# general_purpose_to247_hbridge_rev2.net
KiCad netlist of a schematic drawn in EAGLE
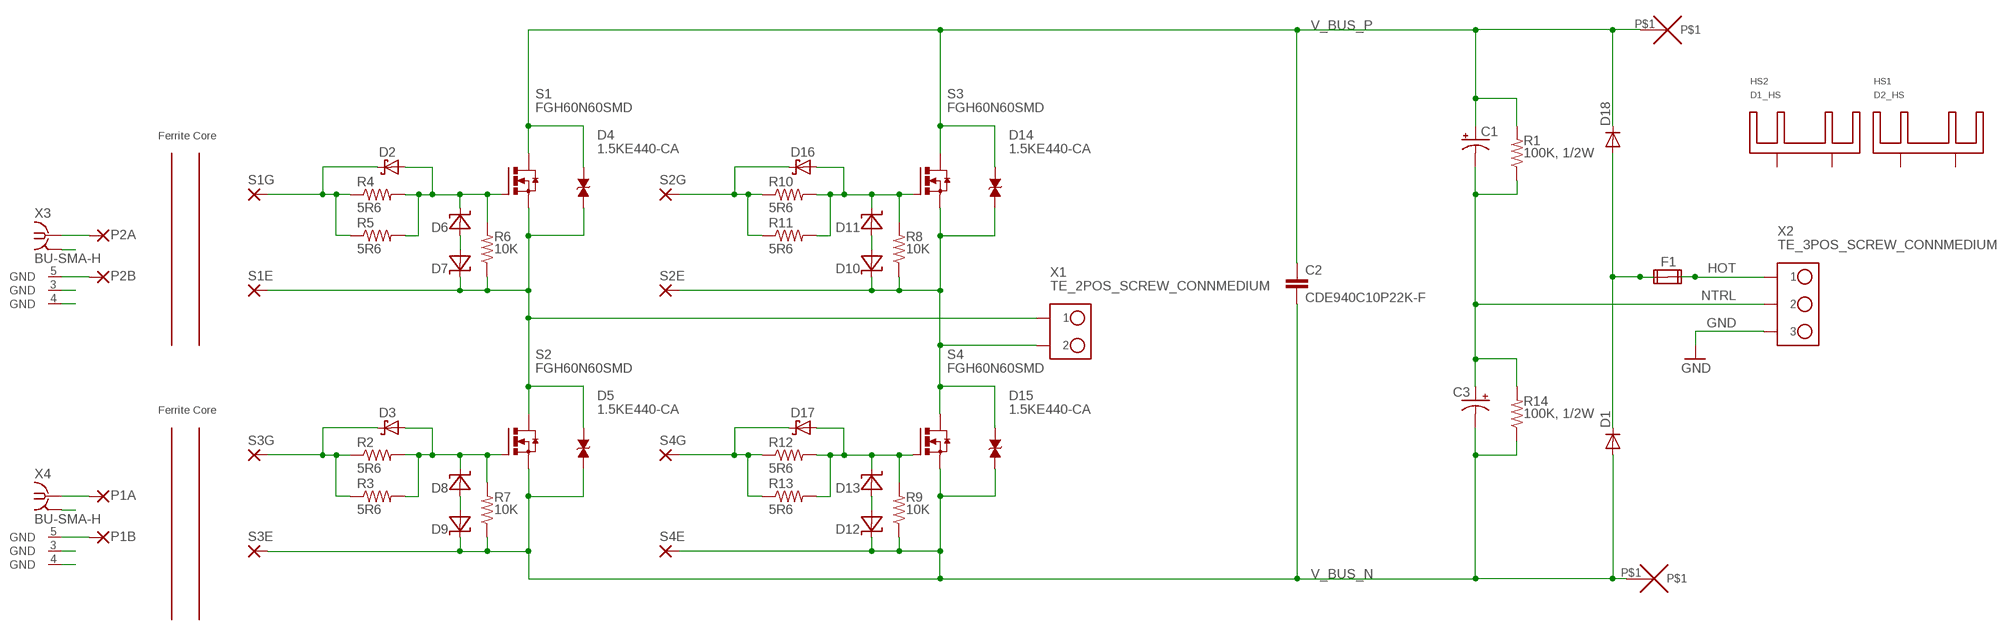
[diagram p0: schematic, sheet 1]

(export (version "E")
  (design (tool "Eeschema 10.0.6"))
  (components
    (comp (ref "C1")
      (value "CPOL-USE10-35")
      (footprint "eagle-import:EB35D")
      (libsource (lib "eagle-import") (part "CPOL-USE10-35"))
    )
    (comp (ref "C2")
      (value "CDE940C10P22K-F")
      (footprint "eagle-import:940C10P22K-F")
      (libsource (lib "eagle-import") (part "CDE940C10P22K-F"))
    )
    (comp (ref "C3")
      (value "CPOL-USE10-35")
      (footprint "eagle-import:EB35D")
      (libsource (lib "eagle-import") (part "CPOL-USE10-35"))
    )
    (comp (ref "D1")
      (value "DIODE-DO220S")
      (footprint "eagle-import:DO220S")
      (libsource (lib "eagle-import") (part "DIODE-DO220S"))
    )
    (comp (ref "D2")
      (value "SCHOTTKY_SMA")
      (footprint "eagle-import:SMA")
      (libsource (lib "eagle-import") (part "SCHOTTKY_SMA"))
    )
    (comp (ref "D3")
      (value "SCHOTTKY_SMA")
      (footprint "eagle-import:SMA")
      (libsource (lib "eagle-import") (part "SCHOTTKY_SMA"))
    )
    (comp (ref "D4")
      (value "1.5KE440-CA")
      (footprint "eagle-import:DO-201_BI")
      (libsource (lib "eagle-import") (part "1.5KEXXX-CA"))
    )
    (comp (ref "D5")
      (value "1.5KE440-CA")
      (footprint "eagle-import:DO-201_BI")
      (libsource (lib "eagle-import") (part "1.5KEXXX-CA"))
    )
    (comp (ref "D6")
      (value "ZENER_SMA")
      (footprint "eagle-import:SMA")
      (libsource (lib "eagle-import") (part "ZENER_SMA"))
    )
    (comp (ref "D7")
      (value "ZENER_SMA")
      (footprint "eagle-import:SMA")
      (libsource (lib "eagle-import") (part "ZENER_SMA"))
    )
    (comp (ref "D8")
      (value "ZENER_SMA")
      (footprint "eagle-import:SMA")
      (libsource (lib "eagle-import") (part "ZENER_SMA"))
    )
    (comp (ref "D9")
      (value "ZENER_SMA")
      (footprint "eagle-import:SMA")
      (libsource (lib "eagle-import") (part "ZENER_SMA"))
    )
    (comp (ref "D10")
      (value "ZENER_SMA")
      (footprint "eagle-import:SMA")
      (libsource (lib "eagle-import") (part "ZENER_SMA"))
    )
    (comp (ref "D11")
      (value "ZENER_SMA")
      (footprint "eagle-import:SMA")
      (libsource (lib "eagle-import") (part "ZENER_SMA"))
    )
    (comp (ref "D12")
      (value "ZENER_SMA")
      (footprint "eagle-import:SMA")
      (libsource (lib "eagle-import") (part "ZENER_SMA"))
    )
    (comp (ref "D13")
      (value "ZENER_SMA")
      (footprint "eagle-import:SMA")
      (libsource (lib "eagle-import") (part "ZENER_SMA"))
    )
    (comp (ref "D14")
      (value "1.5KE440-CA")
      (footprint "eagle-import:DO-201_BI")
      (libsource (lib "eagle-import") (part "1.5KEXXX-CA"))
    )
    (comp (ref "D15")
      (value "1.5KE440-CA")
      (footprint "eagle-import:DO-201_BI")
      (libsource (lib "eagle-import") (part "1.5KEXXX-CA"))
    )
    (comp (ref "D16")
      (value "SCHOTTKY_SMA")
      (footprint "eagle-import:SMA")
      (libsource (lib "eagle-import") (part "SCHOTTKY_SMA"))
    )
    (comp (ref "D17")
      (value "SCHOTTKY_SMA")
      (footprint "eagle-import:SMA")
      (libsource (lib "eagle-import") (part "SCHOTTKY_SMA"))
    )
    (comp (ref "D18")
      (value "DIODE-DO220S")
      (footprint "eagle-import:DO220S")
      (libsource (lib "eagle-import") (part "DIODE-DO220S"))
    )
    (comp (ref "F1")
      (value "FUSE2P")
      (footprint "eagle-import:FUSE1")
      (libsource (lib "eagle-import") (part "FUSE2P"))
    )
    (comp (ref "HS1")
      (value "D2_HS")
      (footprint "eagle-import:V6560_HEATSINK_REVERSED")
      (libsource (lib "eagle-import") (part "HEATSINK_V6560R"))
    )
    (comp (ref "HS2")
      (value "D1_HS")
      (footprint "eagle-import:V6560_HEATSINK_REVERSED")
      (libsource (lib "eagle-import") (part "HEATSINK_V6560R"))
    )
    (comp (ref "P1A")
      (value "SMD5")
      (footprint "eagle-import:SMD2,54-5,08")
      (libsource (lib "eagle-import") (part "SMD5"))
    )
    (comp (ref "P1B")
      (value "SMD5")
      (footprint "eagle-import:SMD2,54-5,08")
      (libsource (lib "eagle-import") (part "SMD5"))
    )
    (comp (ref "P2A")
      (value "SMD5")
      (footprint "eagle-import:SMD2,54-5,08")
      (libsource (lib "eagle-import") (part "SMD5"))
    )
    (comp (ref "P2B")
      (value "SMD5")
      (footprint "eagle-import:SMD2,54-5,08")
      (libsource (lib "eagle-import") (part "SMD5"))
    )
    (comp (ref "R1")
      (value "100K, 1/2W")
      (footprint "eagle-import:0309_12")
      (libsource (lib "eagle-import") (part "R-US_0309/12"))
    )
    (comp (ref "R2")
      (value "5R6")
      (footprint "eagle-import:R2010")
      (libsource (lib "eagle-import") (part "R-US_R2010"))
    )
    (comp (ref "R3")
      (value "5R6")
      (footprint "eagle-import:R0805")
      (libsource (lib "eagle-import") (part "R-US_R0805"))
    )
    (comp (ref "R4")
      (value "5R6")
      (footprint "eagle-import:R2010")
      (libsource (lib "eagle-import") (part "R-US_R2010"))
    )
    (comp (ref "R5")
      (value "5R6")
      (footprint "eagle-import:R0805")
      (libsource (lib "eagle-import") (part "R-US_R0805"))
    )
    (comp (ref "R6")
      (value "10K")
      (footprint "eagle-import:R0805")
      (libsource (lib "eagle-import") (part "R-US_R0805"))
    )
    (comp (ref "R7")
      (value "10K")
      (footprint "eagle-import:R0805")
      (libsource (lib "eagle-import") (part "R-US_R0805"))
    )
    (comp (ref "R8")
      (value "10K")
      (footprint "eagle-import:R0805")
      (libsource (lib "eagle-import") (part "R-US_R0805"))
    )
    (comp (ref "R9")
      (value "10K")
      (footprint "eagle-import:R0805")
      (libsource (lib "eagle-import") (part "R-US_R0805"))
    )
    (comp (ref "R10")
      (value "5R6")
      (footprint "eagle-import:R2010")
      (libsource (lib "eagle-import") (part "R-US_R2010"))
    )
    (comp (ref "R11")
      (value "5R6")
      (footprint "eagle-import:R0805")
      (libsource (lib "eagle-import") (part "R-US_R0805"))
    )
    (comp (ref "R12")
      (value "5R6")
      (footprint "eagle-import:R2010")
      (libsource (lib "eagle-import") (part "R-US_R2010"))
    )
    (comp (ref "R13")
      (value "5R6")
      (footprint "eagle-import:R0805")
      (libsource (lib "eagle-import") (part "R-US_R0805"))
    )
    (comp (ref "R14")
      (value "100K, 1/2W")
      (footprint "eagle-import:0309_12")
      (libsource (lib "eagle-import") (part "R-US_0309/12"))
    )
    (comp (ref "S1")
      (value "FGH60N60SMD")
      (footprint "eagle-import:TO247_H_NOHOLE")
      (libsource (lib "eagle-import") (part "MOSFET-N_TO247"))
    )
    (comp (ref "S1E")
      (value "SMD5")
      (footprint "eagle-import:SMD2,54-5,08")
      (libsource (lib "eagle-import") (part "SMD5"))
    )
    (comp (ref "S1G")
      (value "SMD5")
      (footprint "eagle-import:SMD2,54-5,08")
      (libsource (lib "eagle-import") (part "SMD5"))
    )
    (comp (ref "S2")
      (value "FGH60N60SMD")
      (footprint "eagle-import:TO247_H_NOHOLE")
      (libsource (lib "eagle-import") (part "MOSFET-N_TO247"))
    )
    (comp (ref "S2E")
      (value "SMD5")
      (footprint "eagle-import:SMD2,54-5,08")
      (libsource (lib "eagle-import") (part "SMD5"))
    )
    (comp (ref "S2G")
      (value "SMD5")
      (footprint "eagle-import:SMD2,54-5,08")
      (libsource (lib "eagle-import") (part "SMD5"))
    )
    (comp (ref "S3")
      (value "FGH60N60SMD")
      (footprint "eagle-import:TO247_H_NOHOLE")
      (libsource (lib "eagle-import") (part "MOSFET-N_TO247"))
    )
    (comp (ref "S3E")
      (value "SMD5")
      (footprint "eagle-import:SMD2,54-5,08")
      (libsource (lib "eagle-import") (part "SMD5"))
    )
    (comp (ref "S3G")
      (value "SMD5")
      (footprint "eagle-import:SMD2,54-5,08")
      (libsource (lib "eagle-import") (part "SMD5"))
    )
    (comp (ref "S4")
      (value "FGH60N60SMD")
      (footprint "eagle-import:TO247_H_NOHOLE")
      (libsource (lib "eagle-import") (part "MOSFET-N_TO247"))
    )
    (comp (ref "S4E")
      (value "SMD5")
      (footprint "eagle-import:SMD2,54-5,08")
      (libsource (lib "eagle-import") (part "SMD5"))
    )
    (comp (ref "S4G")
      (value "SMD5")
      (footprint "eagle-import:SMD2,54-5,08")
      (libsource (lib "eagle-import") (part "SMD5"))
    )
    (comp (ref "U$1")
      (value "12AWG_PAD")
      (footprint "eagle-import:12AWG_PAD")
      (libsource (lib "eagle-import") (part "12AWG_PAD"))
    )
    (comp (ref "U$2")
      (value "GDT_SYMBOL")
      (footprint "eagle-import:GDT")
      (libsource (lib "eagle-import") (part "GDT_SYMBOL"))
    )
    (comp (ref "U$3")
      (value "12AWG_PAD")
      (footprint "eagle-import:12AWG_PAD")
      (libsource (lib "eagle-import") (part "12AWG_PAD"))
    )
    (comp (ref "U$4")
      (value "GDT_SYMBOL")
      (footprint "eagle-import:GDT")
      (libsource (lib "eagle-import") (part "GDT_SYMBOL"))
    )
    (comp (ref "X1")
      (value "TE_2POS_SCREW_CONNMEDIUM")
      (footprint "eagle-import:OST_2POS_SCREW_CON_OSTYK51102030")
      (libsource (lib "eagle-import") (part "TE_2POS_SCREW_CONNMEDIUM"))
    )
    (comp (ref "X2")
      (value "TE_3POS_SCREW_CONNMEDIUM")
      (footprint "eagle-import:OST_2POS_SCREW_CON_SOTYK51103030")
      (libsource (lib "eagle-import") (part "TE_3POS_SCREW_CONNMEDIUM"))
    )
    (comp (ref "X3")
      (value "BU-SMA-H")
      (footprint "eagle-import:BU-SMA-H")
      (libsource (lib "eagle-import") (part "BU-SMA-H"))
    )
    (comp (ref "X4")
      (value "BU-SMA-H")
      (footprint "eagle-import:BU-SMA-H")
      (libsource (lib "eagle-import") (part "BU-SMA-H"))
    )
  )
  (nets
    (net (code "1") (name "/HOT") (class "Default")
      (node (ref "F1") (pin "2A") (pinfunction "2A_2A") (pintype "passive"))
      (node (ref "F1") (pin "2B") (pinfunction "2B_2B") (pintype "passive"))
      (node (ref "X2") (pin "P$1") (pinfunction "1_P$1") (pintype "bidirectional"))
    )
    (net (code "2") (name "/NTRL") (class "Default")
      (node (ref "C1") (pin "-") (pinfunction "-_-") (pintype "passive"))
      (node (ref "C3") (pin "+") (pinfunction "+_+") (pintype "passive"))
      (node (ref "R1") (pin "1") (pinfunction "1_1") (pintype "passive"))
      (node (ref "R14") (pin "2") (pinfunction "2_2") (pintype "passive"))
      (node (ref "X2") (pin "P$2") (pinfunction "2_P$2") (pintype "bidirectional"))
    )
    (net (code "3") (name "/V_BUS_N") (class "Default")
      (node (ref "C2") (pin "P$2") (pinfunction "2_P$2") (pintype "passive"))
      (node (ref "C3") (pin "-") (pinfunction "-_-") (pintype "passive"))
      (node (ref "D1") (pin "A") (pinfunction "A_A") (pintype "passive"))
      (node (ref "D12") (pin "C") (pinfunction "C_C") (pintype "passive"))
      (node (ref "D15") (pin "A") (pinfunction "P$1_A") (pintype "bidirectional"))
      (node (ref "D5") (pin "A") (pinfunction "P$1_A") (pintype "bidirectional"))
      (node (ref "D9") (pin "C") (pinfunction "C_C") (pintype "passive"))
      (node (ref "R14") (pin "1") (pinfunction "1_1") (pintype "passive"))
      (node (ref "R7") (pin "1") (pinfunction "1_1") (pintype "passive"))
      (node (ref "R9") (pin "1") (pinfunction "1_1") (pintype "passive"))
      (node (ref "S2") (pin "S") (pinfunction "S_S") (pintype "passive"))
      (node (ref "S3E") (pin "1") (pinfunction "P_1") (pintype "passive"))
      (node (ref "S4") (pin "S") (pinfunction "S_S") (pintype "passive"))
      (node (ref "S4E") (pin "1") (pinfunction "P_1") (pintype "passive"))
      (node (ref "U$1") (pin "P$1") (pinfunction "P$1_P$1") (pintype "bidirectional"))
    )
    (net (code "4") (name "/V_BUS_P") (class "Default")
      (node (ref "C1") (pin "+") (pinfunction "+_+") (pintype "passive"))
      (node (ref "C2") (pin "P$1") (pinfunction "1_P$1") (pintype "passive"))
      (node (ref "D14") (pin "C") (pinfunction "P$2_C") (pintype "bidirectional"))
      (node (ref "D18") (pin "C") (pinfunction "C_C") (pintype "passive"))
      (node (ref "D4") (pin "C") (pinfunction "P$2_C") (pintype "bidirectional"))
      (node (ref "R1") (pin "2") (pinfunction "2_2") (pintype "passive"))
      (node (ref "S1") (pin "D") (pinfunction "D_D") (pintype "passive"))
      (node (ref "S3") (pin "D") (pinfunction "D_D") (pintype "passive"))
      (node (ref "U$3") (pin "P$1") (pinfunction "P$1_P$1") (pintype "bidirectional"))
    )
    (net (code "5") (name "GND") (class "Default")
      (node (ref "X2") (pin "P$3") (pinfunction "3_P$3") (pintype "bidirectional"))
    )
    (net (code "6") (name "Net-(D1-PadC)") (class "Default")
      (node (ref "D1") (pin "C") (pinfunction "C_C") (pintype "passive"))
      (node (ref "D18") (pin "A") (pinfunction "A_A") (pintype "passive"))
      (node (ref "F1") (pin "1A") (pinfunction "1A_1A") (pintype "passive"))
      (node (ref "F1") (pin "1B") (pinfunction "1B_1B") (pintype "passive"))
    )
    (net (code "7") (name "Net-(D2-PadA)") (class "Default")
      (node (ref "D2") (pin "A") (pinfunction "A_A") (pintype "passive"))
      (node (ref "D6") (pin "C") (pinfunction "C_C") (pintype "passive"))
      (node (ref "R4") (pin "2") (pinfunction "2_2") (pintype "passive"))
      (node (ref "R5") (pin "2") (pinfunction "2_2") (pintype "passive"))
      (node (ref "R6") (pin "2") (pinfunction "2_2") (pintype "passive"))
      (node (ref "S1") (pin "G") (pinfunction "G_G") (pintype "passive"))
    )
    (net (code "8") (name "Net-(D3-PadA)") (class "Default")
      (node (ref "D3") (pin "A") (pinfunction "A_A") (pintype "passive"))
      (node (ref "D8") (pin "C") (pinfunction "C_C") (pintype "passive"))
      (node (ref "R2") (pin "2") (pinfunction "2_2") (pintype "passive"))
      (node (ref "R3") (pin "2") (pinfunction "2_2") (pintype "passive"))
      (node (ref "R7") (pin "2") (pinfunction "2_2") (pintype "passive"))
      (node (ref "S2") (pin "G") (pinfunction "G_G") (pintype "passive"))
    )
    (net (code "9") (name "Net-(D4-P$1)") (class "Default")
      (node (ref "D4") (pin "A") (pinfunction "P$1_A") (pintype "bidirectional"))
      (node (ref "D5") (pin "C") (pinfunction "P$2_C") (pintype "bidirectional"))
      (node (ref "D7") (pin "C") (pinfunction "C_C") (pintype "passive"))
      (node (ref "R6") (pin "1") (pinfunction "1_1") (pintype "passive"))
      (node (ref "S1") (pin "S") (pinfunction "S_S") (pintype "passive"))
      (node (ref "S1E") (pin "1") (pinfunction "P_1") (pintype "passive"))
      (node (ref "S2") (pin "D") (pinfunction "D_D") (pintype "passive"))
      (node (ref "X1") (pin "P$1") (pinfunction "1_P$1") (pintype "bidirectional"))
    )
    (net (code "10") (name "Net-(D6-PadA)") (class "Default")
      (node (ref "D6") (pin "A") (pinfunction "A_A") (pintype "passive"))
      (node (ref "D7") (pin "A") (pinfunction "A_A") (pintype "passive"))
    )
    (net (code "11") (name "Net-(D8-PadA)") (class "Default")
      (node (ref "D8") (pin "A") (pinfunction "A_A") (pintype "passive"))
      (node (ref "D9") (pin "A") (pinfunction "A_A") (pintype "passive"))
    )
    (net (code "12") (name "Net-(D10-PadA)") (class "Default")
      (node (ref "D10") (pin "A") (pinfunction "A_A") (pintype "passive"))
      (node (ref "D11") (pin "A") (pinfunction "A_A") (pintype "passive"))
    )
    (net (code "13") (name "Net-(D11-PadC)") (class "Default")
      (node (ref "D11") (pin "C") (pinfunction "C_C") (pintype "passive"))
      (node (ref "D16") (pin "A") (pinfunction "A_A") (pintype "passive"))
      (node (ref "R10") (pin "2") (pinfunction "2_2") (pintype "passive"))
      (node (ref "R11") (pin "2") (pinfunction "2_2") (pintype "passive"))
      (node (ref "R8") (pin "2") (pinfunction "2_2") (pintype "passive"))
      (node (ref "S3") (pin "G") (pinfunction "G_G") (pintype "passive"))
    )
    (net (code "14") (name "Net-(D12-PadA)") (class "Default")
      (node (ref "D12") (pin "A") (pinfunction "A_A") (pintype "passive"))
      (node (ref "D13") (pin "A") (pinfunction "A_A") (pintype "passive"))
    )
    (net (code "15") (name "Net-(D13-PadC)") (class "Default")
      (node (ref "D13") (pin "C") (pinfunction "C_C") (pintype "passive"))
      (node (ref "D17") (pin "A") (pinfunction "A_A") (pintype "passive"))
      (node (ref "R12") (pin "2") (pinfunction "2_2") (pintype "passive"))
      (node (ref "R13") (pin "2") (pinfunction "2_2") (pintype "passive"))
      (node (ref "R9") (pin "2") (pinfunction "2_2") (pintype "passive"))
      (node (ref "S4") (pin "G") (pinfunction "G_G") (pintype "passive"))
    )
    (net (code "16") (name "Net-(D14-P$1)") (class "Default")
      (node (ref "D10") (pin "C") (pinfunction "C_C") (pintype "passive"))
      (node (ref "D14") (pin "A") (pinfunction "P$1_A") (pintype "bidirectional"))
      (node (ref "D15") (pin "C") (pinfunction "P$2_C") (pintype "bidirectional"))
      (node (ref "R8") (pin "1") (pinfunction "1_1") (pintype "passive"))
      (node (ref "S2E") (pin "1") (pinfunction "P_1") (pintype "passive"))
      (node (ref "S3") (pin "S") (pinfunction "S_S") (pintype "passive"))
      (node (ref "S4") (pin "D") (pinfunction "D_D") (pintype "passive"))
      (node (ref "X1") (pin "P$2") (pinfunction "2_P$2") (pintype "bidirectional"))
    )
    (net (code "17") (name "Net-(P1A-P)") (class "Default")
      (node (ref "P1A") (pin "1") (pinfunction "P_1") (pintype "passive"))
      (node (ref "X4") (pin "1") (pinfunction "1_1") (pintype "passive"))
    )
    (net (code "18") (name "Net-(P1B-P)") (class "Default")
      (node (ref "P1B") (pin "1") (pinfunction "P_1") (pintype "passive"))
      (node (ref "X4") (pin "5") (pinfunction "GND_5") (pintype "power_in"))
    )
    (net (code "19") (name "Net-(P2A-P)") (class "Default")
      (node (ref "P2A") (pin "1") (pinfunction "P_1") (pintype "passive"))
      (node (ref "X3") (pin "1") (pinfunction "1_1") (pintype "passive"))
    )
    (net (code "20") (name "Net-(P2B-P)") (class "Default")
      (node (ref "P2B") (pin "1") (pinfunction "P_1") (pintype "passive"))
      (node (ref "X3") (pin "5") (pinfunction "GND_5") (pintype "power_in"))
    )
    (net (code "21") (name "Net-(S1G-P)") (class "Default")
      (node (ref "D2") (pin "C") (pinfunction "C_C") (pintype "passive"))
      (node (ref "R4") (pin "1") (pinfunction "1_1") (pintype "passive"))
      (node (ref "R5") (pin "1") (pinfunction "1_1") (pintype "passive"))
      (node (ref "S1G") (pin "1") (pinfunction "P_1") (pintype "passive"))
    )
    (net (code "22") (name "Net-(S2G-P)") (class "Default")
      (node (ref "D16") (pin "C") (pinfunction "C_C") (pintype "passive"))
      (node (ref "R10") (pin "1") (pinfunction "1_1") (pintype "passive"))
      (node (ref "R11") (pin "1") (pinfunction "1_1") (pintype "passive"))
      (node (ref "S2G") (pin "1") (pinfunction "P_1") (pintype "passive"))
    )
    (net (code "23") (name "Net-(S3G-P)") (class "Default")
      (node (ref "D3") (pin "C") (pinfunction "C_C") (pintype "passive"))
      (node (ref "R2") (pin "1") (pinfunction "1_1") (pintype "passive"))
      (node (ref "R3") (pin "1") (pinfunction "1_1") (pintype "passive"))
      (node (ref "S3G") (pin "1") (pinfunction "P_1") (pintype "passive"))
    )
    (net (code "24") (name "Net-(S4G-P)") (class "Default")
      (node (ref "D17") (pin "C") (pinfunction "C_C") (pintype "passive"))
      (node (ref "R12") (pin "1") (pinfunction "1_1") (pintype "passive"))
      (node (ref "R13") (pin "1") (pinfunction "1_1") (pintype "passive"))
      (node (ref "S4G") (pin "1") (pinfunction "P_1") (pintype "passive"))
    )
    (net (code "25") (name "unconnected-(HS1-P1-PadP$1)") (class "Default")
      (node (ref "HS1") (pin "P$1") (pinfunction "P1_P$1") (pintype "bidirectional"))
    )
    (net (code "26") (name "unconnected-(HS1-P2-PadP$2)") (class "Default")
      (node (ref "HS1") (pin "P$2") (pinfunction "P2_P$2") (pintype "bidirectional"))
    )
    (net (code "27") (name "unconnected-(HS2-P1-PadP$1)") (class "Default")
      (node (ref "HS2") (pin "P$1") (pinfunction "P1_P$1") (pintype "bidirectional"))
    )
    (net (code "28") (name "unconnected-(HS2-P2-PadP$2)") (class "Default")
      (node (ref "HS2") (pin "P$2") (pinfunction "P2_P$2") (pintype "bidirectional"))
    )
    (net (code "29") (name "unconnected-(X3A-GND-Pad2)") (class "Default")
      (node (ref "X3") (pin "2") (pinfunction "GND_2") (pintype "power_in"))
    )
    (net (code "30") (name "unconnected-(X3B-GND-Pad4)") (class "Default")
      (node (ref "X3") (pin "4") (pinfunction "GND_4") (pintype "power_in"))
    )
    (net (code "31") (name "unconnected-(X3C-GND-Pad3)") (class "Default")
      (node (ref "X3") (pin "3") (pinfunction "GND_3") (pintype "power_in"))
    )
    (net (code "32") (name "unconnected-(X4A-GND-Pad2)") (class "Default")
      (node (ref "X4") (pin "2") (pinfunction "GND_2") (pintype "power_in"))
    )
    (net (code "33") (name "unconnected-(X4B-GND-Pad4)") (class "Default")
      (node (ref "X4") (pin "4") (pinfunction "GND_4") (pintype "power_in"))
    )
    (net (code "34") (name "unconnected-(X4C-GND-Pad3)") (class "Default")
      (node (ref "X4") (pin "3") (pinfunction "GND_3") (pintype "power_in"))
    )
  )
)
